# conrad.net
KiCad netlist of a schematic drawn in EAGLE
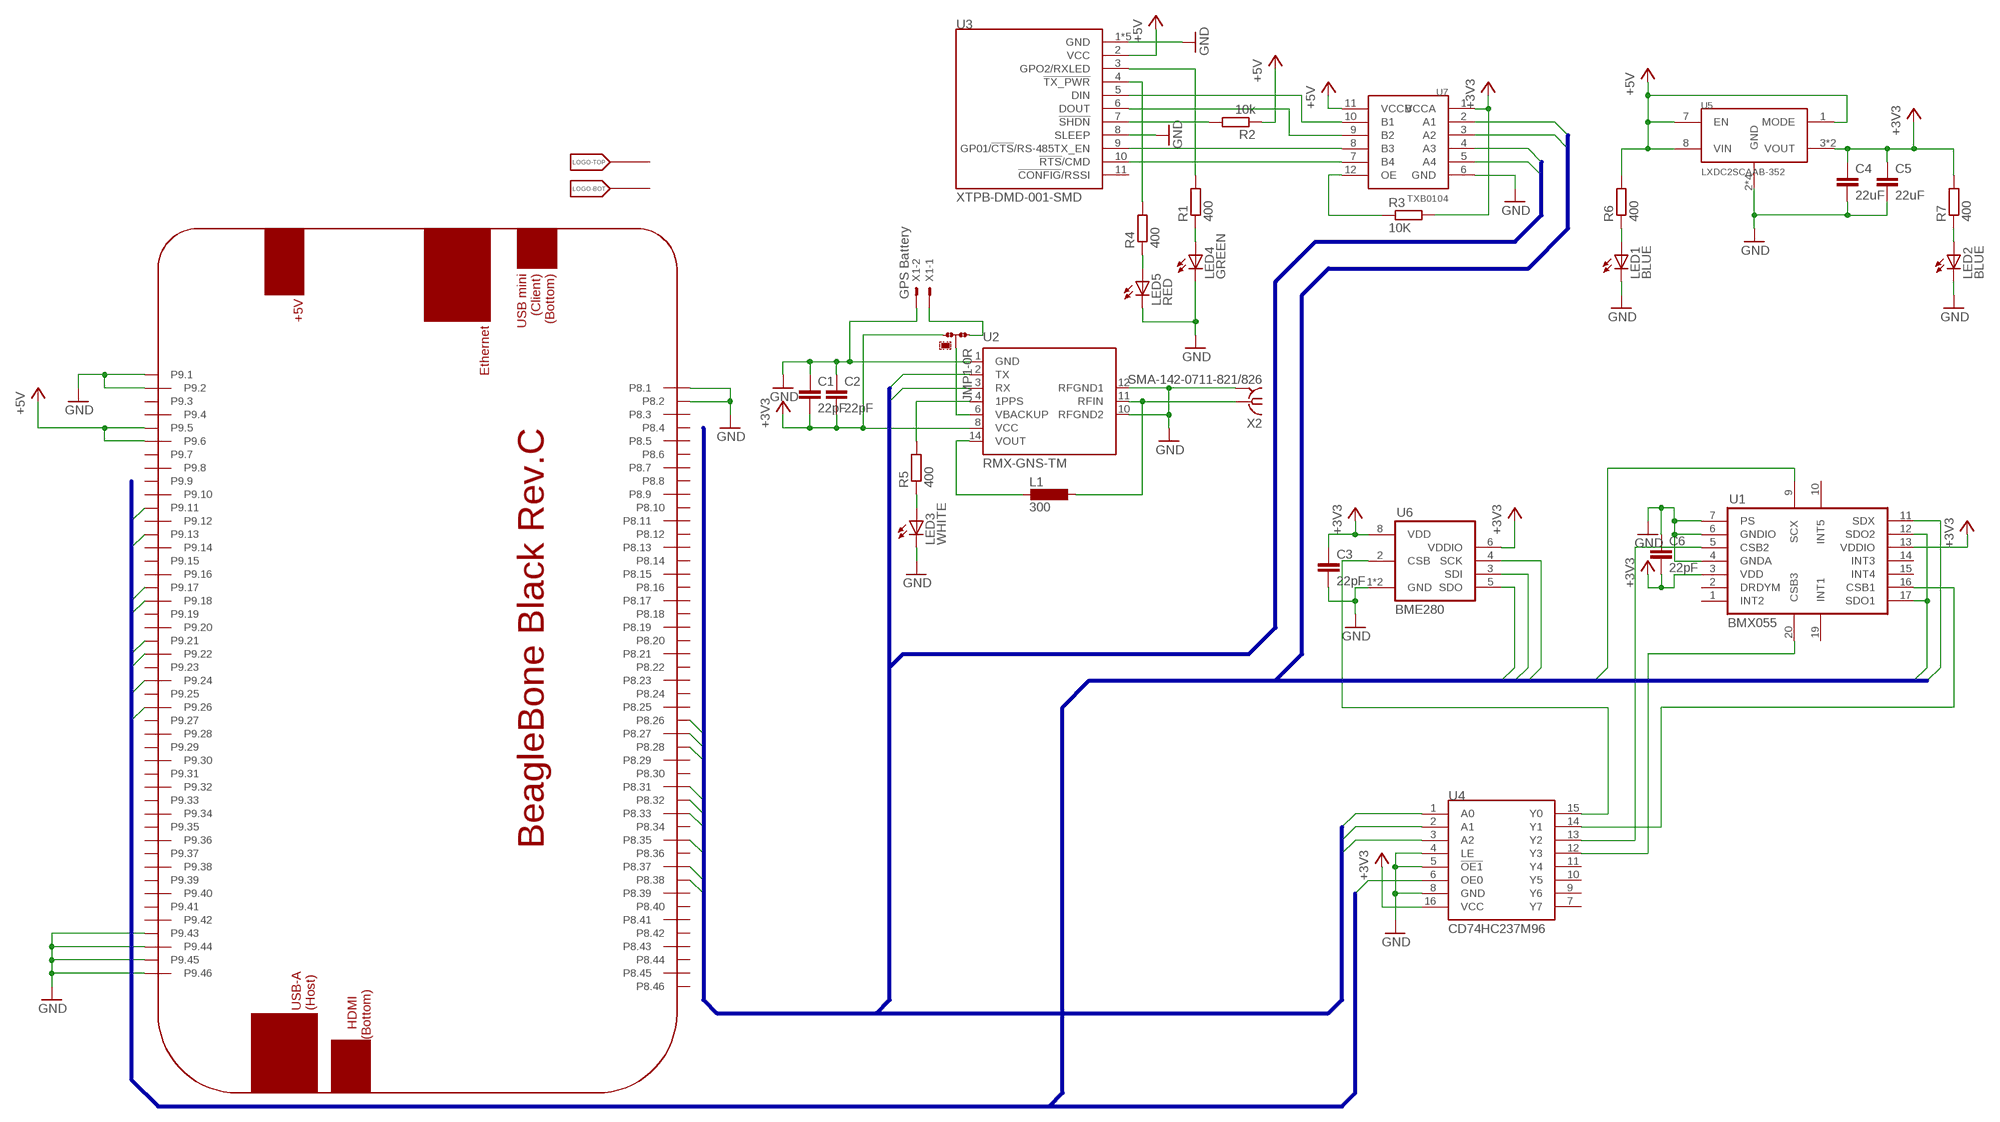
[diagram p0: schematic, sheet 1]

(export (version "E")
  (design (tool "Eeschema 10.0.6"))
  (components
    (comp (ref "C1")
      (value "22pF")
      (footprint "eagle-import:C0603K")
      (libsource (lib "eagle-import") (part "C-EUC0603K"))
    )
    (comp (ref "C2")
      (value "22pF")
      (footprint "eagle-import:C0603K")
      (libsource (lib "eagle-import") (part "C-EUC0603K"))
    )
    (comp (ref "C3")
      (value "22pF")
      (footprint "eagle-import:C0603K")
      (libsource (lib "eagle-import") (part "C-EUC0603K"))
    )
    (comp (ref "C4")
      (value "22uF")
      (footprint "eagle-import:C0603K")
      (libsource (lib "eagle-import") (part "C-EUC0603K"))
    )
    (comp (ref "C5")
      (value "22uF")
      (footprint "eagle-import:C0603K")
      (libsource (lib "eagle-import") (part "C-EUC0603K"))
    )
    (comp (ref "C6")
      (value "22pF")
      (footprint "eagle-import:C0603K")
      (libsource (lib "eagle-import") (part "C-EUC0603K"))
    )
    (comp (ref "JMP1")
      (value "0R-JUMPB")
      (footprint "eagle-import:B0R-JMP")
      (libsource (lib "eagle-import") (part "0R-JUMPB"))
    )
    (comp (ref "L1")
      (value "300")
      (footprint "eagle-import:L0402")
      (libsource (lib "eagle-import") (part "L-EU"))
    )
    (comp (ref "LED1")
      (value "BLUE")
      (footprint "eagle-import:SML0805")
      (libsource (lib "eagle-import") (part "LEDSML0805"))
    )
    (comp (ref "LED2")
      (value "BLUE")
      (footprint "eagle-import:SML0805")
      (libsource (lib "eagle-import") (part "LEDSML0805"))
    )
    (comp (ref "LED3")
      (value "WHITE")
      (footprint "eagle-import:SML0805")
      (libsource (lib "eagle-import") (part "LEDSML0805"))
    )
    (comp (ref "LED4")
      (value "GREEN")
      (footprint "eagle-import:SML0805")
      (libsource (lib "eagle-import") (part "LEDSML0805"))
    )
    (comp (ref "LED5")
      (value "RED")
      (footprint "eagle-import:SML0805")
      (libsource (lib "eagle-import") (part "LEDSML0805"))
    )
    (comp (ref "LOGO")
      (value "SU_LOGO-DUMMY")
      (footprint "eagle-import:SU_LOGO_DS")
      (libsource (lib "eagle-import") (part "SU_LOGO-DUMMY"))
    )
    (comp (ref "PCB1")
      (value "BEAGLEBONE_BLACK_CAPE")
      (footprint "eagle-import:BEAGLEBONE_BLACK_CAPE")
      (libsource (lib "eagle-import") (part "BEAGLEBONE_BLACK_CAPE"))
    )
    (comp (ref "R1")
      (value "400")
      (footprint "eagle-import:R0603")
      (libsource (lib "eagle-import") (part "R-EU_R0603"))
    )
    (comp (ref "R2")
      (value "10k")
      (footprint "eagle-import:R0603")
      (libsource (lib "eagle-import") (part "R-EU_R0603"))
    )
    (comp (ref "R3")
      (value "10K")
      (footprint "eagle-import:R0603")
      (libsource (lib "eagle-import") (part "R-EU_R0603"))
    )
    (comp (ref "R4")
      (value "400")
      (footprint "eagle-import:R0603")
      (libsource (lib "eagle-import") (part "R-EU_R0603"))
    )
    (comp (ref "R5")
      (value "400")
      (footprint "eagle-import:R0603")
      (libsource (lib "eagle-import") (part "R-EU_R0603"))
    )
    (comp (ref "R6")
      (value "400")
      (footprint "eagle-import:R0603")
      (libsource (lib "eagle-import") (part "R-EU_R0603"))
    )
    (comp (ref "R7")
      (value "400")
      (footprint "eagle-import:R0603")
      (libsource (lib "eagle-import") (part "R-EU_R0603"))
    )
    (comp (ref "U1")
      (value "BMX055")
      (footprint "eagle-import:BMX055")
      (libsource (lib "eagle-import") (part "BMX055"))
    )
    (comp (ref "U2")
      (value "RMX-GNS-TM")
      (footprint "eagle-import:RMX-GNSS-TM")
      (libsource (lib "eagle-import") (part "RMX-GNS-TM"))
    )
    (comp (ref "U3")
      (value "XTPB-DMD-001-SMD")
      (footprint "eagle-import:XTP9B-DMS-001-SMD")
      (libsource (lib "eagle-import") (part "XTPB-DMD-001-SMD"))
    )
    (comp (ref "U4")
      (value "CD74HC237M96")
      (footprint "eagle-import:SO-16")
      (libsource (lib "eagle-import") (part "CD74HC237M96"))
    )
    (comp (ref "U5")
      (value "LXDC2SCAAB-352")
      (footprint "eagle-import:LXDC2SCAAB-352")
      (libsource (lib "eagle-import") (part "LXDC2SCAAB-352"))
    )
    (comp (ref "U6")
      (value "BME280")
      (footprint "eagle-import:BME280")
      (libsource (lib "eagle-import") (part "BME280"))
    )
    (comp (ref "U7")
      (value "TXB0104")
      (footprint "eagle-import:R-PUQFN-N12")
      (libsource (lib "eagle-import") (part "TXB0104"))
    )
    (comp (ref "X1")
      (value "GPS Battery")
      (footprint "eagle-import:15-91-02")
      (libsource (lib "eagle-import") (part "C-GRID-02-15-19"))
    )
    (comp (ref "X2")
      (value "SMA-142-0711-821/826")
      (footprint "eagle-import:J502-ND-142-0711-821_826")
      (fields (field (name "MF") "JOHNSON COMPONENTS") (field (name "MPN") "142-0711-821"))
      (libsource (lib "eagle-import") (part "SMA-142-0711-821/826"))
    )
  )
  (nets
    (net (code "1") (name "+3V3") (class "Default")
      (node (ref "C1") (pin "2") (pinfunction "2_2") (pintype "passive"))
      (node (ref "C2") (pin "2") (pinfunction "2_2") (pintype "passive"))
      (node (ref "C3") (pin "1") (pinfunction "1_1") (pintype "passive"))
      (node (ref "C4") (pin "1") (pinfunction "1_1") (pintype "passive"))
      (node (ref "C5") (pin "1") (pinfunction "1_1") (pintype "passive"))
      (node (ref "C6") (pin "2") (pinfunction "2_2") (pintype "passive"))
      (node (ref "JMP1") (pin "3") (pinfunction "3_3") (pintype "passive"))
      (node (ref "R3") (pin "2") (pinfunction "2_2") (pintype "passive"))
      (node (ref "R7") (pin "2") (pinfunction "2_2") (pintype "passive"))
      (node (ref "U1") (pin "13") (pinfunction "VDDIO_13") (pintype "power_in"))
      (node (ref "U1") (pin "3") (pinfunction "VDD_3") (pintype "power_in"))
      (node (ref "U2") (pin "8") (pinfunction "VCC_8") (pintype "power_in"))
      (node (ref "U4") (pin "16") (pinfunction "VCC_16") (pintype "power_in"))
      (node (ref "U5") (pin "3") (pinfunction "VOUT_3") (pintype "power_in"))
      (node (ref "U5") (pin "4") (pinfunction "VOUT_4") (pintype "power_in"))
      (node (ref "U6") (pin "6") (pinfunction "VDDIO_6") (pintype "power_in"))
      (node (ref "U6") (pin "8") (pinfunction "VDD_8") (pintype "power_in"))
      (node (ref "U7") (pin "1") (pinfunction "VCCA_1") (pintype "power_in"))
    )
    (net (code "2") (name "+5V") (class "Default")
      (node (ref "PCB1") (pin "P9.5") (pinfunction "P9.5_P9.5") (pintype "bidirectional"))
      (node (ref "PCB1") (pin "P9.6") (pinfunction "P9.6_P9.6") (pintype "bidirectional"))
      (node (ref "R2") (pin "1") (pinfunction "1_1") (pintype "passive"))
      (node (ref "R6") (pin "2") (pinfunction "2_2") (pintype "passive"))
      (node (ref "U3") (pin "2") (pinfunction "VCC_2") (pintype "power_in"))
      (node (ref "U5") (pin "1") (pinfunction "MODE_1") (pintype "input"))
      (node (ref "U5") (pin "7") (pinfunction "EN_7") (pintype "input"))
      (node (ref "U5") (pin "8") (pinfunction "VIN_8") (pintype "power_in"))
      (node (ref "U7") (pin "11") (pinfunction "VCCB_11") (pintype "power_in"))
    )
    (net (code "3") (name "/SPI0_CS0") (class "Default")
      (node (ref "PCB1") (pin "P9.17") (pinfunction "P9.17_P9.17") (pintype "bidirectional"))
      (node (ref "U4") (pin "6") (pinfunction "OE0_6") (pintype "input"))
    )
    (net (code "4") (name "/SPI0_D0") (class "Default")
      (node (ref "PCB1") (pin "P9.21") (pinfunction "P9.21_P9.21") (pintype "bidirectional"))
      (node (ref "U1") (pin "12") (pinfunction "SDO2_12") (pintype "output"))
      (node (ref "U1") (pin "17") (pinfunction "SDO1_17") (pintype "output"))
      (node (ref "U6") (pin "5") (pinfunction "SDO_5") (pintype "input"))
    )
    (net (code "5") (name "/SPI0_D1") (class "Default")
      (node (ref "PCB1") (pin "P9.18") (pinfunction "P9.18_P9.18") (pintype "bidirectional"))
      (node (ref "U1") (pin "11") (pinfunction "SDX_11") (pintype "bidirectional"))
      (node (ref "U6") (pin "3") (pinfunction "SDI_3") (pintype "bidirectional"))
    )
    (net (code "6") (name "/SPI0_SCLK") (class "Default")
      (node (ref "PCB1") (pin "P9.22") (pinfunction "P9.22_P9.22") (pintype "bidirectional"))
      (node (ref "U1") (pin "9") (pinfunction "SCX_9") (pintype "input"))
      (node (ref "U6") (pin "4") (pinfunction "SCK_4") (pintype "bidirectional"))
    )
    (net (code "7") (name "/SPI_CSB26") (class "Default")
      (node (ref "PCB1") (pin "P8.26") (pinfunction "P8.26_P8.26") (pintype "bidirectional"))
      (node (ref "U4") (pin "1") (pinfunction "A0_1") (pintype "input"))
    )
    (net (code "8") (name "/SPI_CSB27") (class "Default")
      (node (ref "PCB1") (pin "P8.27") (pinfunction "P8.27_P8.27") (pintype "bidirectional"))
      (node (ref "U4") (pin "2") (pinfunction "A1_2") (pintype "input"))
    )
    (net (code "9") (name "/SPI_CSB28") (class "Default")
      (node (ref "PCB1") (pin "P8.28") (pinfunction "P8.28_P8.28") (pintype "bidirectional"))
      (node (ref "U4") (pin "3") (pinfunction "A2_3") (pintype "input"))
    )
    (net (code "10") (name "/UART4_CTSN") (class "Default")
      (node (ref "PCB1") (pin "P8.35") (pinfunction "P8.35_P8.35") (pintype "bidirectional"))
      (node (ref "U7") (pin "4") (pinfunction "A3_4") (pintype "bidirectional"))
    )
    (net (code "11") (name "/UART4_RTSN") (class "Default")
      (node (ref "PCB1") (pin "P8.33") (pinfunction "P8.33_P8.33") (pintype "bidirectional"))
      (node (ref "U7") (pin "5") (pinfunction "A4_5") (pintype "bidirectional"))
    )
    (net (code "12") (name "/UART4_RXD") (class "Default")
      (node (ref "PCB1") (pin "P9.11") (pinfunction "P9.11_P9.11") (pintype "bidirectional"))
      (node (ref "U7") (pin "3") (pinfunction "A2_3") (pintype "bidirectional"))
    )
    (net (code "13") (name "/UART4_TXD") (class "Default")
      (node (ref "PCB1") (pin "P9.13") (pinfunction "P9.13_P9.13") (pintype "bidirectional"))
      (node (ref "U7") (pin "2") (pinfunction "A1_2") (pintype "bidirectional"))
    )
    (net (code "14") (name "/UART5_RXD") (class "Default")
      (node (ref "PCB1") (pin "P8.38") (pinfunction "P8.38_P8.38") (pintype "bidirectional"))
      (node (ref "U2") (pin "2") (pinfunction "TX_2") (pintype "output"))
    )
    (net (code "15") (name "/UART5_TXD") (class "Default")
      (node (ref "PCB1") (pin "P8.37") (pinfunction "P8.37_P8.37") (pintype "bidirectional"))
      (node (ref "U2") (pin "3") (pinfunction "RX_3") (pintype "input"))
    )
    (net (code "16") (name "GND") (class "Default")
      (node (ref "C1") (pin "1") (pinfunction "1_1") (pintype "passive"))
      (node (ref "C2") (pin "1") (pinfunction "1_1") (pintype "passive"))
      (node (ref "C3") (pin "2") (pinfunction "2_2") (pintype "passive"))
      (node (ref "C4") (pin "2") (pinfunction "2_2") (pintype "passive"))
      (node (ref "C5") (pin "2") (pinfunction "2_2") (pintype "passive"))
      (node (ref "C6") (pin "1") (pinfunction "1_1") (pintype "passive"))
      (node (ref "LED1") (pin "C") (pinfunction "C_C") (pintype "passive"))
      (node (ref "LED2") (pin "C") (pinfunction "C_C") (pintype "passive"))
      (node (ref "LED3") (pin "C") (pinfunction "C_C") (pintype "passive"))
      (node (ref "LED4") (pin "C") (pinfunction "C_C") (pintype "passive"))
      (node (ref "LED5") (pin "C") (pinfunction "C_C") (pintype "passive"))
      (node (ref "PCB1") (pin "P8.1") (pinfunction "P8.1_P8.1") (pintype "bidirectional"))
      (node (ref "PCB1") (pin "P8.2") (pinfunction "P8.2_P8.2") (pintype "bidirectional"))
      (node (ref "PCB1") (pin "P9.1") (pinfunction "P9.1_P9.1") (pintype "bidirectional"))
      (node (ref "PCB1") (pin "P9.2") (pinfunction "P9.2_P9.2") (pintype "bidirectional"))
      (node (ref "PCB1") (pin "P9.43") (pinfunction "P9.43_P9.43") (pintype "bidirectional"))
      (node (ref "PCB1") (pin "P9.44") (pinfunction "P9.44_P9.44") (pintype "bidirectional"))
      (node (ref "PCB1") (pin "P9.45") (pinfunction "P9.45_P9.45") (pintype "bidirectional"))
      (node (ref "PCB1") (pin "P9.46") (pinfunction "P9.46_P9.46") (pintype "bidirectional"))
      (node (ref "U1") (pin "4") (pinfunction "GNDA_4") (pintype "power_in"))
      (node (ref "U1") (pin "6") (pinfunction "GNDIO_6") (pintype "bidirectional"))
      (node (ref "U1") (pin "7") (pinfunction "PS_7") (pintype "input"))
      (node (ref "U2") (pin "1") (pinfunction "GND_1") (pintype "power_in"))
      (node (ref "U2") (pin "10") (pinfunction "RFGND2_10") (pintype "power_in"))
      (node (ref "U2") (pin "12") (pinfunction "RFGND1_12") (pintype "power_in"))
      (node (ref "U3") (pin "1") (pinfunction "GND_1") (pintype "power_in"))
      (node (ref "U3") (pin "8") (pinfunction "SLEEP_8") (pintype "input"))
      (node (ref "U3") (pin "P$1") (pinfunction "GND_P$1") (pintype "power_in"))
      (node (ref "U3") (pin "P$2") (pinfunction "GND_P$2") (pintype "power_in"))
      (node (ref "U3") (pin "P$3") (pinfunction "GND_P$3") (pintype "power_in"))
      (node (ref "U3") (pin "P$4") (pinfunction "GND_P$4") (pintype "power_in"))
      (node (ref "U4") (pin "4") (pinfunction "LE_4") (pintype "input"))
      (node (ref "U4") (pin "5") (pinfunction "~{OE1}_5") (pintype "input"))
      (node (ref "U4") (pin "8") (pinfunction "GND_8") (pintype "power_in"))
      (node (ref "U5") (pin "2") (pinfunction "GND_2") (pintype "power_in"))
      (node (ref "U5") (pin "5") (pinfunction "GND_5") (pintype "power_in"))
      (node (ref "U5") (pin "6") (pinfunction "GND_6") (pintype "power_in"))
      (node (ref "U5") (pin "9") (pinfunction "GND_9") (pintype "power_in"))
      (node (ref "U6") (pin "1") (pinfunction "GND_1") (pintype "power_in"))
      (node (ref "U6") (pin "7") (pinfunction "GND_7") (pintype "power_in"))
      (node (ref "U7") (pin "6") (pinfunction "GND_6") (pintype "power_in"))
      (node (ref "X1") (pin "2") (pinfunction "S_2") (pintype "passive"))
      (node (ref "X2") (pin "G@1") (pinfunction "2_G@1") (pintype "passive"))
      (node (ref "X2") (pin "G@2") (pinfunction "2_G@2") (pintype "passive"))
      (node (ref "X2") (pin "G@3") (pinfunction "2_G@3") (pintype "passive"))
      (node (ref "X2") (pin "G@4") (pinfunction "2_G@4") (pintype "passive"))
    )
    (net (code "17") (name "Net-(LED1-PadA)") (class "Default")
      (node (ref "LED1") (pin "A") (pinfunction "A_A") (pintype "passive"))
      (node (ref "R6") (pin "1") (pinfunction "1_1") (pintype "passive"))
    )
    (net (code "18") (name "Net-(LED2-PadA)") (class "Default")
      (node (ref "LED2") (pin "A") (pinfunction "A_A") (pintype "passive"))
      (node (ref "R7") (pin "1") (pinfunction "1_1") (pintype "passive"))
    )
    (net (code "19") (name "Net-(LED3-PadA)") (class "Default")
      (node (ref "LED3") (pin "A") (pinfunction "A_A") (pintype "passive"))
      (node (ref "R5") (pin "1") (pinfunction "1_1") (pintype "passive"))
    )
    (net (code "20") (name "Net-(LED4-PadA)") (class "Default")
      (node (ref "LED4") (pin "A") (pinfunction "A_A") (pintype "passive"))
      (node (ref "R1") (pin "1") (pinfunction "1_1") (pintype "passive"))
    )
    (net (code "21") (name "Net-(LED5-PadA)") (class "Default")
      (node (ref "LED5") (pin "A") (pinfunction "A_A") (pintype "passive"))
      (node (ref "R4") (pin "1") (pinfunction "1_1") (pintype "passive"))
    )
    (net (code "22") (name "Net-(U1-CSB1)") (class "Default")
      (node (ref "U1") (pin "16") (pinfunction "CSB1_16") (pintype "input"))
      (node (ref "U4") (pin "14") (pinfunction "Y1_14") (pintype "output"))
    )
    (net (code "23") (name "Net-(U1-CSB2)") (class "Default")
      (node (ref "U1") (pin "5") (pinfunction "CSB2_5") (pintype "input"))
      (node (ref "U4") (pin "13") (pinfunction "Y2_13") (pintype "output"))
    )
    (net (code "24") (name "Net-(U1-CSB3)") (class "Default")
      (node (ref "U1") (pin "20") (pinfunction "CSB3_20") (pintype "input"))
      (node (ref "U4") (pin "12") (pinfunction "Y3_12") (pintype "output"))
    )
    (net (code "25") (name "Net-(U2-1PPS)") (class "Default")
      (node (ref "R5") (pin "2") (pinfunction "2_2") (pintype "passive"))
      (node (ref "U2") (pin "4") (pinfunction "1PPS_4") (pintype "output"))
    )
    (net (code "26") (name "Net-(U2-RFIN)") (class "Default")
      (node (ref "L1") (pin "1") (pinfunction "1_1") (pintype "passive"))
      (node (ref "U2") (pin "11") (pinfunction "RFIN_11") (pintype "input"))
      (node (ref "X2") (pin "1") (pinfunction "1_1") (pintype "passive"))
    )
    (net (code "27") (name "Net-(U2-VBACKUP)") (class "Default")
      (node (ref "JMP1") (pin "2") (pinfunction "2_2") (pintype "passive"))
      (node (ref "U2") (pin "6") (pinfunction "VBACKUP_6") (pintype "power_in"))
    )
    (net (code "28") (name "Net-(U2-VOUT)") (class "Default")
      (node (ref "L1") (pin "2") (pinfunction "2_2") (pintype "passive"))
      (node (ref "U2") (pin "14") (pinfunction "VOUT_14") (pintype "output"))
    )
    (net (code "29") (name "Net-(U3-DIN)") (class "Default")
      (node (ref "U3") (pin "5") (pinfunction "DIN_5") (pintype "input"))
      (node (ref "U7") (pin "10") (pinfunction "B1_10") (pintype "bidirectional"))
    )
    (net (code "30") (name "Net-(U3-DOUT)") (class "Default")
      (node (ref "U3") (pin "6") (pinfunction "DOUT_6") (pintype "output"))
      (node (ref "U7") (pin "9") (pinfunction "B2_9") (pintype "bidirectional"))
    )
    (net (code "31") (name "Net-(U3-GP01{slash}~{CTS}{slash}RS-485TX_EN)") (class "Default")
      (node (ref "U3") (pin "9") (pinfunction "GP01/~{CTS}/RS-485TX_EN_9") (pintype "output"))
      (node (ref "U7") (pin "8") (pinfunction "B3_8") (pintype "bidirectional"))
    )
    (net (code "32") (name "Net-(U3-GPO2{slash}RXLED)") (class "Default")
      (node (ref "R1") (pin "2") (pinfunction "2_2") (pintype "passive"))
      (node (ref "U3") (pin "3") (pinfunction "GPO2/RXLED_3") (pintype "output"))
    )
    (net (code "33") (name "Net-(U3-~{RTS}{slash}CMD)") (class "Default")
      (node (ref "U3") (pin "10") (pinfunction "~{RTS}/CMD_10") (pintype "input"))
      (node (ref "U7") (pin "7") (pinfunction "B4_7") (pintype "bidirectional"))
    )
    (net (code "34") (name "Net-(U3-~{SHDN})") (class "Default")
      (node (ref "R2") (pin "2") (pinfunction "2_2") (pintype "passive"))
      (node (ref "U3") (pin "7") (pinfunction "~{SHDN}_7") (pintype "input"))
    )
    (net (code "35") (name "Net-(U3-~{TX_PWR})") (class "Default")
      (node (ref "R4") (pin "2") (pinfunction "2_2") (pintype "passive"))
      (node (ref "U3") (pin "4") (pinfunction "~{TX_PWR}_4") (pintype "output"))
    )
    (net (code "36") (name "Net-(U4-Y0)") (class "Default")
      (node (ref "U4") (pin "15") (pinfunction "Y0_15") (pintype "output"))
      (node (ref "U6") (pin "2") (pinfunction "CSB_2") (pintype "input"))
    )
    (net (code "37") (name "Net-(U7-OE)") (class "Default")
      (node (ref "R3") (pin "1") (pinfunction "1_1") (pintype "passive"))
      (node (ref "U7") (pin "12") (pinfunction "OE_12") (pintype "input"))
    )
    (net (code "38") (name "Net-(X1A-S)") (class "Default")
      (node (ref "JMP1") (pin "1") (pinfunction "1_1") (pintype "passive"))
      (node (ref "X1") (pin "1") (pinfunction "S_1") (pintype "passive"))
    )
    (net (code "39") (name "unconnected-(LOGO-PadP$1)") (class "Default")
      (node (ref "LOGO") (pin "P$1") (pinfunction "P$1_P$1") (pintype "bidirectional"))
    )
    (net (code "40") (name "unconnected-(LOGOA-P$1-PadP$2)") (class "Default")
      (node (ref "LOGO") (pin "P$2") (pinfunction "P$1_P$2") (pintype "bidirectional"))
    )
    (net (code "41") (name "unconnected-(PCB1-PadP8.3)") (class "Default")
      (node (ref "PCB1") (pin "P8.3") (pinfunction "P8.3_P8.3") (pintype "bidirectional"))
    )
    (net (code "42") (name "unconnected-(PCB1-PadP8.4)") (class "Default")
      (node (ref "PCB1") (pin "P8.4") (pinfunction "P8.4_P8.4") (pintype "bidirectional"))
    )
    (net (code "43") (name "unconnected-(PCB1-PadP8.5)") (class "Default")
      (node (ref "PCB1") (pin "P8.5") (pinfunction "P8.5_P8.5") (pintype "bidirectional"))
    )
    (net (code "44") (name "unconnected-(PCB1-PadP8.6)") (class "Default")
      (node (ref "PCB1") (pin "P8.6") (pinfunction "P8.6_P8.6") (pintype "bidirectional"))
    )
    (net (code "45") (name "unconnected-(PCB1-PadP8.7)") (class "Default")
      (node (ref "PCB1") (pin "P8.7") (pinfunction "P8.7_P8.7") (pintype "bidirectional"))
    )
    (net (code "46") (name "unconnected-(PCB1-PadP8.8)") (class "Default")
      (node (ref "PCB1") (pin "P8.8") (pinfunction "P8.8_P8.8") (pintype "bidirectional"))
    )
    (net (code "47") (name "unconnected-(PCB1-PadP8.9)") (class "Default")
      (node (ref "PCB1") (pin "P8.9") (pinfunction "P8.9_P8.9") (pintype "bidirectional"))
    )
    (net (code "48") (name "unconnected-(PCB1-PadP8.10)") (class "Default")
      (node (ref "PCB1") (pin "P8.10") (pinfunction "P8.10_P8.10") (pintype "bidirectional"))
    )
    (net (code "49") (name "unconnected-(PCB1-PadP8.11)") (class "Default")
      (node (ref "PCB1") (pin "P8.11") (pinfunction "P8.11_P8.11") (pintype "bidirectional"))
    )
    (net (code "50") (name "unconnected-(PCB1-PadP8.12)") (class "Default")
      (node (ref "PCB1") (pin "P8.12") (pinfunction "P8.12_P8.12") (pintype "bidirectional"))
    )
    (net (code "51") (name "unconnected-(PCB1-PadP8.13)") (class "Default")
      (node (ref "PCB1") (pin "P8.13") (pinfunction "P8.13_P8.13") (pintype "bidirectional"))
    )
    (net (code "52") (name "unconnected-(PCB1-PadP8.14)") (class "Default")
      (node (ref "PCB1") (pin "P8.14") (pinfunction "P8.14_P8.14") (pintype "bidirectional"))
    )
    (net (code "53") (name "unconnected-(PCB1-PadP8.15)") (class "Default")
      (node (ref "PCB1") (pin "P8.15") (pinfunction "P8.15_P8.15") (pintype "bidirectional"))
    )
    (net (code "54") (name "unconnected-(PCB1-PadP8.16)") (class "Default")
      (node (ref "PCB1") (pin "P8.16") (pinfunction "P8.16_P8.16") (pintype "bidirectional"))
    )
    (net (code "55") (name "unconnected-(PCB1-PadP8.17)") (class "Default")
      (node (ref "PCB1") (pin "P8.17") (pinfunction "P8.17_P8.17") (pintype "bidirectional"))
    )
    (net (code "56") (name "unconnected-(PCB1-PadP8.18)") (class "Default")
      (node (ref "PCB1") (pin "P8.18") (pinfunction "P8.18_P8.18") (pintype "bidirectional"))
    )
    (net (code "57") (name "unconnected-(PCB1-PadP8.19)") (class "Default")
      (node (ref "PCB1") (pin "P8.19") (pinfunction "P8.19_P8.19") (pintype "bidirectional"))
    )
    (net (code "58") (name "unconnected-(PCB1-PadP8.20)") (class "Default")
      (node (ref "PCB1") (pin "P8.20") (pinfunction "P8.20_P8.20") (pintype "bidirectional"))
    )
    (net (code "59") (name "unconnected-(PCB1-PadP8.21)") (class "Default")
      (node (ref "PCB1") (pin "P8.21") (pinfunction "P8.21_P8.21") (pintype "bidirectional"))
    )
    (net (code "60") (name "unconnected-(PCB1-PadP8.22)") (class "Default")
      (node (ref "PCB1") (pin "P8.22") (pinfunction "P8.22_P8.22") (pintype "bidirectional"))
    )
    (net (code "61") (name "unconnected-(PCB1-PadP8.23)") (class "Default")
      (node (ref "PCB1") (pin "P8.23") (pinfunction "P8.23_P8.23") (pintype "bidirectional"))
    )
    (net (code "62") (name "unconnected-(PCB1-PadP8.24)") (class "Default")
      (node (ref "PCB1") (pin "P8.24") (pinfunction "P8.24_P8.24") (pintype "bidirectional"))
    )
    (net (code "63") (name "unconnected-(PCB1-PadP8.25)") (class "Default")
      (node (ref "PCB1") (pin "P8.25") (pinfunction "P8.25_P8.25") (pintype "bidirectional"))
    )
    (net (code "64") (name "unconnected-(PCB1-PadP8.29)") (class "Default")
      (node (ref "PCB1") (pin "P8.29") (pinfunction "P8.29_P8.29") (pintype "bidirectional"))
    )
    (net (code "65") (name "unconnected-(PCB1-PadP8.30)") (class "Default")
      (node (ref "PCB1") (pin "P8.30") (pinfunction "P8.30_P8.30") (pintype "bidirectional"))
    )
    (net (code "66") (name "unconnected-(PCB1-PadP8.31)") (class "Default")
      (node (ref "PCB1") (pin "P8.31") (pinfunction "P8.31_P8.31") (pintype "bidirectional"))
    )
    (net (code "67") (name "unconnected-(PCB1-PadP8.32)") (class "Default")
      (node (ref "PCB1") (pin "P8.32") (pinfunction "P8.32_P8.32") (pintype "bidirectional"))
    )
    (net (code "68") (name "unconnected-(PCB1-PadP8.34)") (class "Default")
      (node (ref "PCB1") (pin "P8.34") (pinfunction "P8.34_P8.34") (pintype "bidirectional"))
    )
    (net (code "69") (name "unconnected-(PCB1-PadP8.36)") (class "Default")
      (node (ref "PCB1") (pin "P8.36") (pinfunction "P8.36_P8.36") (pintype "bidirectional"))
    )
    (net (code "70") (name "unconnected-(PCB1-PadP8.39)") (class "Default")
      (node (ref "PCB1") (pin "P8.39") (pinfunction "P8.39_P8.39") (pintype "bidirectional"))
    )
    (net (code "71") (name "unconnected-(PCB1-PadP8.40)") (class "Default")
      (node (ref "PCB1") (pin "P8.40") (pinfunction "P8.40_P8.40") (pintype "bidirectional"))
    )
    (net (code "72") (name "unconnected-(PCB1-PadP8.41)") (class "Default")
      (node (ref "PCB1") (pin "P8.41") (pinfunction "P8.41_P8.41") (pintype "bidirectional"))
    )
    (net (code "73") (name "unconnected-(PCB1-PadP8.42)") (class "Default")
      (node (ref "PCB1") (pin "P8.42") (pinfunction "P8.42_P8.42") (pintype "bidirectional"))
    )
    (net (code "74") (name "unconnected-(PCB1-PadP8.43)") (class "Default")
      (node (ref "PCB1") (pin "P8.43") (pinfunction "P8.43_P8.43") (pintype "bidirectional"))
    )
    (net (code "75") (name "unconnected-(PCB1-PadP8.44)") (class "Default")
      (node (ref "PCB1") (pin "P8.44") (pinfunction "P8.44_P8.44") (pintype "bidirectional"))
    )
    (net (code "76") (name "unconnected-(PCB1-PadP8.45)") (class "Default")
      (node (ref "PCB1") (pin "P8.45") (pinfunction "P8.45_P8.45") (pintype "bidirectional"))
    )
    (net (code "77") (name "unconnected-(PCB1-PadP8.46)") (class "Default")
      (node (ref "PCB1") (pin "P8.46") (pinfunction "P8.46_P8.46") (pintype "bidirectional"))
    )
    (net (code "78") (name "unconnected-(PCB1-PadP9.3)") (class "Default")
      (node (ref "PCB1") (pin "P9.3") (pinfunction "P9.3_P9.3") (pintype "bidirectional"))
    )
    (net (code "79") (name "unconnected-(PCB1-PadP9.4)") (class "Default")
      (node (ref "PCB1") (pin "P9.4") (pinfunction "P9.4_P9.4") (pintype "bidirectional"))
    )
    (net (code "80") (name "unconnected-(PCB1-PadP9.7)") (class "Default")
      (node (ref "PCB1") (pin "P9.7") (pinfunction "P9.7_P9.7") (pintype "bidirectional"))
    )
    (net (code "81") (name "unconnected-(PCB1-PadP9.8)") (class "Default")
      (node (ref "PCB1") (pin "P9.8") (pinfunction "P9.8_P9.8") (pintype "bidirectional"))
    )
    (net (code "82") (name "unconnected-(PCB1-PadP9.9)") (class "Default")
      (node (ref "PCB1") (pin "P9.9") (pinfunction "P9.9_P9.9") (pintype "bidirectional"))
    )
    (net (code "83") (name "unconnected-(PCB1-PadP9.10)") (class "Default")
      (node (ref "PCB1") (pin "P9.10") (pinfunction "P9.10_P9.10") (pintype "bidirectional"))
    )
    (net (code "84") (name "unconnected-(PCB1-PadP9.12)") (class "Default")
      (node (ref "PCB1") (pin "P9.12") (pinfunction "P9.12_P9.12") (pintype "bidirectional"))
    )
    (net (code "85") (name "unconnected-(PCB1-PadP9.14)") (class "Default")
      (node (ref "PCB1") (pin "P9.14") (pinfunction "P9.14_P9.14") (pintype "bidirectional"))
    )
    (net (code "86") (name "unconnected-(PCB1-PadP9.15)") (class "Default")
      (node (ref "PCB1") (pin "P9.15") (pinfunction "P9.15_P9.15") (pintype "bidirectional"))
    )
    (net (code "87") (name "unconnected-(PCB1-PadP9.16)") (class "Default")
      (node (ref "PCB1") (pin "P9.16") (pinfunction "P9.16_P9.16") (pintype "bidirectional"))
    )
    (net (code "88") (name "unconnected-(PCB1-PadP9.19)") (class "Default")
      (node (ref "PCB1") (pin "P9.19") (pinfunction "P9.19_P9.19") (pintype "bidirectional"))
    )
    (net (code "89") (name "unconnected-(PCB1-PadP9.20)") (class "Default")
      (node (ref "PCB1") (pin "P9.20") (pinfunction "P9.20_P9.20") (pintype "bidirectional"))
    )
    (net (code "90") (name "unconnected-(PCB1-PadP9.23)") (class "Default")
      (node (ref "PCB1") (pin "P9.23") (pinfunction "P9.23_P9.23") (pintype "bidirectional"))
    )
    (net (code "91") (name "unconnected-(PCB1-PadP9.24)") (class "Default")
      (node (ref "PCB1") (pin "P9.24") (pinfunction "P9.24_P9.24") (pintype "bidirectional"))
    )
    (net (code "92") (name "unconnected-(PCB1-PadP9.25)") (class "Default")
      (node (ref "PCB1") (pin "P9.25") (pinfunction "P9.25_P9.25") (pintype "bidirectional"))
    )
    (net (code "93") (name "unconnected-(PCB1-PadP9.26)") (class "Default")
      (node (ref "PCB1") (pin "P9.26") (pinfunction "P9.26_P9.26") (pintype "bidirectional"))
    )
    (net (code "94") (name "unconnected-(PCB1-PadP9.27)") (class "Default")
      (node (ref "PCB1") (pin "P9.27") (pinfunction "P9.27_P9.27") (pintype "bidirectional"))
    )
    (net (code "95") (name "unconnected-(PCB1-PadP9.28)") (class "Default")
      (node (ref "PCB1") (pin "P9.28") (pinfunction "P9.28_P9.28") (pintype "bidirectional"))
    )
    (net (code "96") (name "unconnected-(PCB1-PadP9.29)") (class "Default")
      (node (ref "PCB1") (pin "P9.29") (pinfunction "P9.29_P9.29") (pintype "bidirectional"))
    )
    (net (code "97") (name "unconnected-(PCB1-PadP9.30)") (class "Default")
      (node (ref "PCB1") (pin "P9.30") (pinfunction "P9.30_P9.30") (pintype "bidirectional"))
    )
    (net (code "98") (name "unconnected-(PCB1-PadP9.31)") (class "Default")
      (node (ref "PCB1") (pin "P9.31") (pinfunction "P9.31_P9.31") (pintype "bidirectional"))
    )
    (net (code "99") (name "unconnected-(PCB1-PadP9.32)") (class "Default")
      (node (ref "PCB1") (pin "P9.32") (pinfunction "P9.32_P9.32") (pintype "bidirectional"))
    )
    (net (code "100") (name "unconnected-(PCB1-PadP9.33)") (class "Default")
      (node (ref "PCB1") (pin "P9.33") (pinfunction "P9.33_P9.33") (pintype "bidirectional"))
    )
    (net (code "101") (name "unconnected-(PCB1-PadP9.34)") (class "Default")
      (node (ref "PCB1") (pin "P9.34") (pinfunction "P9.34_P9.34") (pintype "bidirectional"))
    )
    (net (code "102") (name "unconnected-(PCB1-PadP9.35)") (class "Default")
      (node (ref "PCB1") (pin "P9.35") (pinfunction "P9.35_P9.35") (pintype "bidirectional"))
    )
    (net (code "103") (name "unconnected-(PCB1-PadP9.36)") (class "Default")
      (node (ref "PCB1") (pin "P9.36") (pinfunction "P9.36_P9.36") (pintype "bidirectional"))
    )
    (net (code "104") (name "unconnected-(PCB1-PadP9.37)") (class "Default")
      (node (ref "PCB1") (pin "P9.37") (pinfunction "P9.37_P9.37") (pintype "bidirectional"))
    )
    (net (code "105") (name "unconnected-(PCB1-PadP9.38)") (class "Default")
      (node (ref "PCB1") (pin "P9.38") (pinfunction "P9.38_P9.38") (pintype "bidirectional"))
    )
    (net (code "106") (name "unconnected-(PCB1-PadP9.39)") (class "Default")
      (node (ref "PCB1") (pin "P9.39") (pinfunction "P9.39_P9.39") (pintype "bidirectional"))
    )
    (net (code "107") (name "unconnected-(PCB1-PadP9.40)") (class "Default")
      (node (ref "PCB1") (pin "P9.40") (pinfunction "P9.40_P9.40") (pintype "bidirectional"))
    )
    (net (code "108") (name "unconnected-(PCB1-PadP9.41)") (class "Default")
      (node (ref "PCB1") (pin "P9.41") (pinfunction "P9.41_P9.41") (pintype "bidirectional"))
    )
    (net (code "109") (name "unconnected-(PCB1-PadP9.42)") (class "Default")
      (node (ref "PCB1") (pin "P9.42") (pinfunction "P9.42_P9.42") (pintype "bidirectional"))
    )
    (net (code "110") (name "unconnected-(U1-DRDYM-Pad2)") (class "Default")
      (node (ref "U1") (pin "2") (pinfunction "DRDYM_2") (pintype "output"))
    )
    (net (code "111") (name "unconnected-(U1-INT1-Pad19)") (class "Default")
      (node (ref "U1") (pin "19") (pinfunction "INT1_19") (pintype "output"))
    )
    (net (code "112") (name "unconnected-(U1-INT2-Pad1)") (class "Default")
      (node (ref "U1") (pin "1") (pinfunction "INT2_1") (pintype "output"))
    )
    (net (code "113") (name "unconnected-(U1-INT3-Pad14)") (class "Default")
      (node (ref "U1") (pin "14") (pinfunction "INT3_14") (pintype "bidirectional"))
    )
    (net (code "114") (name "unconnected-(U1-INT4-Pad15)") (class "Default")
      (node (ref "U1") (pin "15") (pinfunction "INT4_15") (pintype "bidirectional"))
    )
    (net (code "115") (name "unconnected-(U1-INT5-Pad10)") (class "Default")
      (node (ref "U1") (pin "10") (pinfunction "INT5_10") (pintype "output"))
    )
    (net (code "116") (name "unconnected-(U3-~{CONFIG}{slash}RSSI-Pad11)") (class "Default")
      (node (ref "U3") (pin "11") (pinfunction "~{CONFIG}/RSSI_11") (pintype "bidirectional"))
    )
    (net (code "117") (name "unconnected-(U4-Y4-Pad11)") (class "Default")
      (node (ref "U4") (pin "11") (pinfunction "Y4_11") (pintype "output"))
    )
    (net (code "118") (name "unconnected-(U4-Y5-Pad10)") (class "Default")
      (node (ref "U4") (pin "10") (pinfunction "Y5_10") (pintype "output"))
    )
    (net (code "119") (name "unconnected-(U4-Y6-Pad9)") (class "Default")
      (node (ref "U4") (pin "9") (pinfunction "Y6_9") (pintype "output"))
    )
    (net (code "120") (name "unconnected-(U4-Y7-Pad7)") (class "Default")
      (node (ref "U4") (pin "7") (pinfunction "Y7_7") (pintype "output"))
    )
  )
)
